# design.net
KiCad netlist of a schematic drawn in Altium Designer
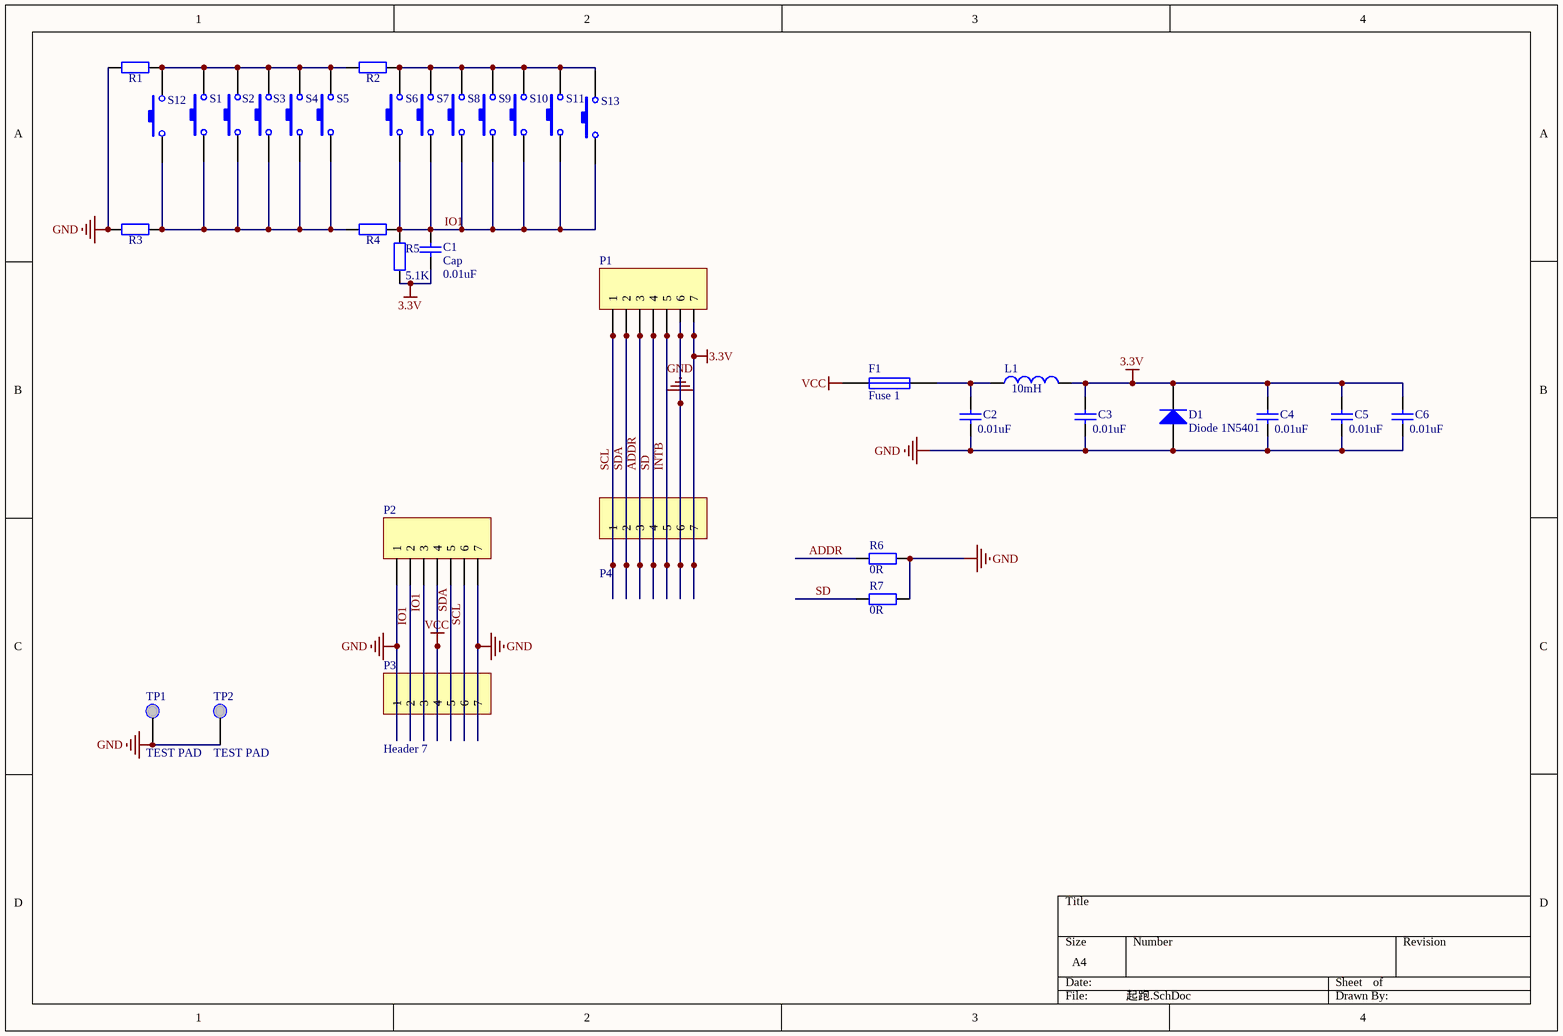
[diagram p0: 起跑.SchDoc]

(export (version "E")
  (design (tool "Eeschema 10.0.6"))
  (components
    (comp (ref "C1")
      (value "Cap")
      (footprint "C2012")
      (description "Capacitor")
      (fields (field (name "ALTIUM_VALUE") "0.01uF") (field (name "PUBLISHER") "Altium Limited"))
      (libsource (lib "Miscellaneous Devices") (part "Cap"))
    )
    (comp (ref "C2")
      (value "0.01uF")
      (footprint "c2012")
      (description "Capacitor")
      (fields (field (name "Comment") "Cap") (field (name "PUBLISHER") "Altium Limited"))
      (libsource (lib "Miscellaneous Devices") (part "Cap"))
    )
    (comp (ref "C3")
      (value "0.01uF")
      (footprint "C2012")
      (description "Capacitor")
      (fields (field (name "Comment") "Cap") (field (name "PUBLISHER") "Altium Limited"))
      (libsource (lib "Miscellaneous Devices") (part "Cap"))
    )
    (comp (ref "C4")
      (value "0.01uF")
      (footprint "C2012")
      (description "Capacitor")
      (fields (field (name "Comment") "Cap") (field (name "PUBLISHER") "Altium Limited"))
      (libsource (lib "Miscellaneous Devices") (part "Cap"))
    )
    (comp (ref "C5")
      (value "0.01uF")
      (footprint "C2012")
      (description "Capacitor")
      (fields (field (name "Comment") "Cap") (field (name "PUBLISHER") "Altium Limited"))
      (libsource (lib "Miscellaneous Devices") (part "Cap"))
    )
    (comp (ref "C6")
      (value "0.01uF")
      (footprint "C2012")
      (description "Capacitor")
      (fields (field (name "Comment") "Cap") (field (name "PUBLISHER") "Altium Limited"))
      (libsource (lib "Miscellaneous Devices") (part "Cap"))
    )
    (comp (ref "D1")
      (value "Diode 1N5401")
      (footprint "1206(2)")
      (description "3 Amp General Purpose Rectifier")
      (fields (field (name "PUBLISHER") "Altium Limited"))
      (libsource (lib "Miscellaneous Devices") (part "Diode 1N5401"))
    )
    (comp (ref "F1")
      (value "Fuse 1")
      (footprint "r2012")
      (description "Fuse")
      (fields (field (name "PUBLISHER") "Altium Limited"))
      (libsource (lib "Miscellaneous Devices") (part "Fuse 1"))
    )
    (comp (ref "L1")
      (value "10mH")
      (footprint "r2012")
      (description "Inductor")
      (fields (field (name "PUBLISHER") "Altium Limited"))
      (libsource (lib "Miscellaneous Devices") (part "Inductor"))
    )
    (comp (ref "P1")
      (value "Header 7H")
      (footprint "HDR1X7H")
      (description "Header, 7-Pin, Right Angle")
      (fields (field (name "PUBLISHER") "Altium Limited"))
      (libsource (lib "Miscellaneous Connectors") (part "Header 7H"))
    )
    (comp (ref "P2")
      (value "Header 7")
      (footprint "HDR1X7")
      (description "Header, 7-Pin")
      (fields (field (name "PUBLISHER") "Altium Limited"))
      (libsource (lib "Sparks") (part "Header 7"))
    )
    (comp (ref "P3")
      (value "Header 7")
      (footprint "FFC/SM1.0-2H7")
      (description "Header, 7-Pin")
      (fields (field (name "PUBLISHER") "Altium Limited"))
      (libsource (lib "Sparks") (part "Header 7"))
    )
    (comp (ref "P4")
      (value "Header 7")
      (footprint "HDR1X7")
      (description "Header, 7-Pin")
      (fields (field (name "PUBLISHER") "Altium Limited"))
      (libsource (lib "Sparks") (part "Header 7"))
    )
    (comp (ref "R1")
      (value "Res2")
      (footprint "R2012")
      (description "Resistor")
      (fields (field (name "PUBLISHER") "Altium Limited"))
      (libsource (lib "Miscellaneous Devices") (part "Res2"))
    )
    (comp (ref "R2")
      (value "Res2")
      (footprint "R2012")
      (description "Resistor")
      (fields (field (name "PUBLISHER") "Altium Limited"))
      (libsource (lib "Miscellaneous Devices") (part "Res2"))
    )
    (comp (ref "R3")
      (value "Res2")
      (footprint "R2012")
      (description "Resistor")
      (fields (field (name "PUBLISHER") "Altium Limited"))
      (libsource (lib "Miscellaneous Devices") (part "Res2"))
    )
    (comp (ref "R4")
      (value "Res2")
      (footprint "R2012")
      (description "Resistor")
      (fields (field (name "PUBLISHER") "Altium Limited"))
      (libsource (lib "Miscellaneous Devices") (part "Res2"))
    )
    (comp (ref "R5")
      (value "5.1K")
      (footprint "R2012")
      (description "Resistor")
      (fields (field (name "Comment") "Res2") (field (name "PUBLISHER") "Altium Limited"))
      (libsource (lib "") (part "Res2_1"))
    )
    (comp (ref "R6")
      (value "0R")
      (footprint "1206(2)")
      (description "Resistor")
      (libsource (lib "K60-V4.0") (part "Res"))
    )
    (comp (ref "R7")
      (value "0R")
      (footprint "1206(2)")
      (description "Resistor")
      (libsource (lib "K60-V4.0") (part "Res"))
    )
    (comp (ref "S1")
      (value "SW-PB")
      (footprint "AXIAL-0.9")
      (description "Switch")
      (fields (field (name "PUBLISHER") "Altium Limited"))
      (libsource (lib "Miscellaneous Devices") (part "SW-PB"))
    )
    (comp (ref "S2")
      (value "SW-PB")
      (footprint "AXIAL-0.9")
      (description "Switch")
      (fields (field (name "PUBLISHER") "Altium Limited"))
      (libsource (lib "Miscellaneous Devices") (part "SW-PB"))
    )
    (comp (ref "S3")
      (value "SW-PB")
      (footprint "AXIAL-0.9")
      (description "Switch")
      (fields (field (name "PUBLISHER") "Altium Limited"))
      (libsource (lib "Miscellaneous Devices") (part "SW-PB"))
    )
    (comp (ref "S4")
      (value "SW-PB")
      (footprint "AXIAL-0.9")
      (description "Switch")
      (fields (field (name "PUBLISHER") "Altium Limited"))
      (libsource (lib "Miscellaneous Devices") (part "SW-PB"))
    )
    (comp (ref "S5")
      (value "SW-PB")
      (footprint "AXIAL-0.9")
      (description "Switch")
      (fields (field (name "PUBLISHER") "Altium Limited"))
      (libsource (lib "Miscellaneous Devices") (part "SW-PB"))
    )
    (comp (ref "S6")
      (value "SW-PB")
      (footprint "AXIAL-0.9")
      (description "Switch")
      (fields (field (name "PUBLISHER") "Altium Limited"))
      (libsource (lib "Miscellaneous Devices") (part "SW-PB"))
    )
    (comp (ref "S7")
      (value "SW-PB")
      (footprint "AXIAL-0.9")
      (description "Switch")
      (fields (field (name "PUBLISHER") "Altium Limited"))
      (libsource (lib "Miscellaneous Devices") (part "SW-PB"))
    )
    (comp (ref "S8")
      (value "SW-PB")
      (footprint "AXIAL-0.9")
      (description "Switch")
      (fields (field (name "PUBLISHER") "Altium Limited"))
      (libsource (lib "Miscellaneous Devices") (part "SW-PB"))
    )
    (comp (ref "S9")
      (value "SW-PB")
      (footprint "AXIAL-0.9")
      (description "Switch")
      (fields (field (name "PUBLISHER") "Altium Limited"))
      (libsource (lib "Miscellaneous Devices") (part "SW-PB"))
    )
    (comp (ref "S10")
      (value "SW-PB")
      (footprint "AXIAL-0.9")
      (description "Switch")
      (fields (field (name "PUBLISHER") "Altium Limited"))
      (libsource (lib "Miscellaneous Devices") (part "SW-PB"))
    )
    (comp (ref "S11")
      (value "SW-PB")
      (footprint "AXIAL-0.9")
      (description "Switch")
      (fields (field (name "PUBLISHER") "Altium Limited"))
      (libsource (lib "Miscellaneous Devices") (part "SW-PB"))
    )
    (comp (ref "S12")
      (value "SW-PB")
      (footprint "AXIAL-0.9")
      (description "Switch")
      (fields (field (name "PUBLISHER") "Altium Limited"))
      (libsource (lib "Miscellaneous Devices") (part "SW-PB"))
    )
    (comp (ref "S13")
      (value "SW-PB")
      (footprint "AXIAL-0.9")
      (description "Switch")
      (fields (field (name "PUBLISHER") "Altium Limited"))
      (libsource (lib "Miscellaneous Devices") (part "SW-PB"))
    )
    (comp (ref "TP1") (value "TEST PAD") (footprint "M3") (libsource (lib "刘爽") (part "TEST PAD")))
    (comp (ref "TP2") (value "TEST PAD") (footprint "M3") (libsource (lib "刘爽") (part "TEST PAD")))
  )
  (nets
    (net (code "1") (name "/ADDR") (class "Default")
      (node (ref "P1") (pin "3") (pinfunction "3_3") (pintype "passive"))
      (node (ref "P4") (pin "3") (pinfunction "3_3") (pintype "passive"))
      (node (ref "R6") (pin "1") (pinfunction "1_1") (pintype "passive"))
    )
    (net (code "2") (name "/INTB") (class "Default")
      (node (ref "P1") (pin "5") (pinfunction "5_5") (pintype "passive"))
      (node (ref "P4") (pin "5") (pinfunction "5_5") (pintype "passive"))
    )
    (net (code "3") (name "/IO1") (class "Default")
      (node (ref "C1") (pin "2") (pinfunction "2_2") (pintype "passive"))
      (node (ref "P2") (pin "2") (pinfunction "2_2") (pintype "passive"))
      (node (ref "P2") (pin "3") (pinfunction "3_3") (pintype "passive"))
      (node (ref "P3") (pin "2") (pinfunction "2_2") (pintype "passive"))
      (node (ref "P3") (pin "3") (pinfunction "3_3") (pintype "passive"))
      (node (ref "R4") (pin "1") (pinfunction "1_1") (pintype "passive"))
      (node (ref "R5") (pin "2") (pinfunction "2_2") (pintype "passive"))
      (node (ref "S10") (pin "1") (pinfunction "1_1") (pintype "passive"))
      (node (ref "S11") (pin "1") (pinfunction "1_1") (pintype "passive"))
      (node (ref "S13") (pin "1") (pinfunction "1_1") (pintype "passive"))
      (node (ref "S6") (pin "1") (pinfunction "1_1") (pintype "passive"))
      (node (ref "S7") (pin "1") (pinfunction "1_1") (pintype "passive"))
      (node (ref "S8") (pin "1") (pinfunction "1_1") (pintype "passive"))
      (node (ref "S9") (pin "1") (pinfunction "1_1") (pintype "passive"))
    )
    (net (code "4") (name "/SCL") (class "Default")
      (node (ref "P1") (pin "1") (pinfunction "1_1") (pintype "passive"))
      (node (ref "P2") (pin "6") (pinfunction "6_6") (pintype "passive"))
      (node (ref "P3") (pin "6") (pinfunction "6_6") (pintype "passive"))
      (node (ref "P4") (pin "1") (pinfunction "1_1") (pintype "passive"))
    )
    (net (code "5") (name "/SD") (class "Default")
      (node (ref "P1") (pin "4") (pinfunction "4_4") (pintype "passive"))
      (node (ref "P4") (pin "4") (pinfunction "4_4") (pintype "passive"))
      (node (ref "R7") (pin "1") (pinfunction "1_1") (pintype "passive"))
    )
    (net (code "6") (name "/SDA") (class "Default")
      (node (ref "P1") (pin "2") (pinfunction "2_2") (pintype "passive"))
      (node (ref "P2") (pin "5") (pinfunction "5_5") (pintype "passive"))
      (node (ref "P3") (pin "5") (pinfunction "5_5") (pintype "passive"))
      (node (ref "P4") (pin "2") (pinfunction "2_2") (pintype "passive"))
    )
    (net (code "7") (name "3.3V") (class "Default")
      (node (ref "C1") (pin "1") (pinfunction "1_1") (pintype "passive"))
      (node (ref "C3") (pin "2") (pinfunction "2_2") (pintype "passive"))
      (node (ref "C4") (pin "2") (pinfunction "2_2") (pintype "passive"))
      (node (ref "C5") (pin "2") (pinfunction "2_2") (pintype "passive"))
      (node (ref "C6") (pin "2") (pinfunction "2_2") (pintype "passive"))
      (node (ref "D1") (pin "2") (pinfunction "K_2") (pintype "passive"))
      (node (ref "L1") (pin "2") (pinfunction "2_2") (pintype "passive"))
      (node (ref "P1") (pin "7") (pinfunction "7_7") (pintype "passive"))
      (node (ref "P4") (pin "7") (pinfunction "7_7") (pintype "passive"))
      (node (ref "R5") (pin "1") (pinfunction "1_1") (pintype "passive"))
    )
    (net (code "8") (name "GND") (class "Default")
      (node (ref "C2") (pin "1") (pinfunction "1_1") (pintype "passive"))
      (node (ref "C3") (pin "1") (pinfunction "1_1") (pintype "passive"))
      (node (ref "C4") (pin "1") (pinfunction "1_1") (pintype "passive"))
      (node (ref "C5") (pin "1") (pinfunction "1_1") (pintype "passive"))
      (node (ref "C6") (pin "1") (pinfunction "1_1") (pintype "passive"))
      (node (ref "D1") (pin "1") (pinfunction "A_1") (pintype "passive"))
      (node (ref "P1") (pin "6") (pinfunction "6_6") (pintype "passive"))
      (node (ref "P2") (pin "1") (pinfunction "1_1") (pintype "passive"))
      (node (ref "P2") (pin "7") (pinfunction "7_7") (pintype "passive"))
      (node (ref "P3") (pin "1") (pinfunction "1_1") (pintype "passive"))
      (node (ref "P3") (pin "7") (pinfunction "7_7") (pintype "passive"))
      (node (ref "P4") (pin "6") (pinfunction "6_6") (pintype "passive"))
      (node (ref "R1") (pin "2") (pinfunction "2_2") (pintype "passive"))
      (node (ref "R3") (pin "2") (pinfunction "2_2") (pintype "passive"))
      (node (ref "R6") (pin "2") (pinfunction "2_2") (pintype "passive"))
      (node (ref "R7") (pin "2") (pinfunction "2_2") (pintype "passive"))
      (node (ref "TP1") (pin "1") (pinfunction "1_1") (pintype "passive"))
      (node (ref "TP2") (pin "1") (pinfunction "1_1") (pintype "passive"))
    )
    (net (code "9") (name "Net-(C2-Pad2)") (class "Default")
      (node (ref "C2") (pin "2") (pinfunction "2_2") (pintype "passive"))
      (node (ref "F1") (pin "2") (pinfunction "2_2") (pintype "passive"))
      (node (ref "L1") (pin "1") (pinfunction "1_1") (pintype "passive"))
    )
    (net (code "10") (name "Net-(R1-Pad1)") (class "Default")
      (node (ref "R1") (pin "1") (pinfunction "1_1") (pintype "passive"))
      (node (ref "R2") (pin "2") (pinfunction "2_2") (pintype "passive"))
      (node (ref "S1") (pin "2") (pinfunction "2_2") (pintype "passive"))
      (node (ref "S12") (pin "2") (pinfunction "2_2") (pintype "passive"))
      (node (ref "S2") (pin "2") (pinfunction "2_2") (pintype "passive"))
      (node (ref "S3") (pin "2") (pinfunction "2_2") (pintype "passive"))
      (node (ref "S4") (pin "2") (pinfunction "2_2") (pintype "passive"))
      (node (ref "S5") (pin "2") (pinfunction "2_2") (pintype "passive"))
    )
    (net (code "11") (name "Net-(R2-Pad1)") (class "Default")
      (node (ref "R2") (pin "1") (pinfunction "1_1") (pintype "passive"))
      (node (ref "S10") (pin "2") (pinfunction "2_2") (pintype "passive"))
      (node (ref "S11") (pin "2") (pinfunction "2_2") (pintype "passive"))
      (node (ref "S13") (pin "2") (pinfunction "2_2") (pintype "passive"))
      (node (ref "S6") (pin "2") (pinfunction "2_2") (pintype "passive"))
      (node (ref "S7") (pin "2") (pinfunction "2_2") (pintype "passive"))
      (node (ref "S8") (pin "2") (pinfunction "2_2") (pintype "passive"))
      (node (ref "S9") (pin "2") (pinfunction "2_2") (pintype "passive"))
    )
    (net (code "12") (name "Net-(R3-Pad1)") (class "Default")
      (node (ref "R3") (pin "1") (pinfunction "1_1") (pintype "passive"))
      (node (ref "R4") (pin "2") (pinfunction "2_2") (pintype "passive"))
      (node (ref "S1") (pin "1") (pinfunction "1_1") (pintype "passive"))
      (node (ref "S12") (pin "1") (pinfunction "1_1") (pintype "passive"))
      (node (ref "S2") (pin "1") (pinfunction "1_1") (pintype "passive"))
      (node (ref "S3") (pin "1") (pinfunction "1_1") (pintype "passive"))
      (node (ref "S4") (pin "1") (pinfunction "1_1") (pintype "passive"))
      (node (ref "S5") (pin "1") (pinfunction "1_1") (pintype "passive"))
    )
    (net (code "13") (name "VCC") (class "Default")
      (node (ref "F1") (pin "1") (pinfunction "1_1") (pintype "passive"))
      (node (ref "P2") (pin "4") (pinfunction "4_4") (pintype "passive"))
      (node (ref "P3") (pin "4") (pinfunction "4_4") (pintype "passive"))
    )
  )
)
